# schema4.net
KiCad netlist of a schematic drawn in Altium Designer
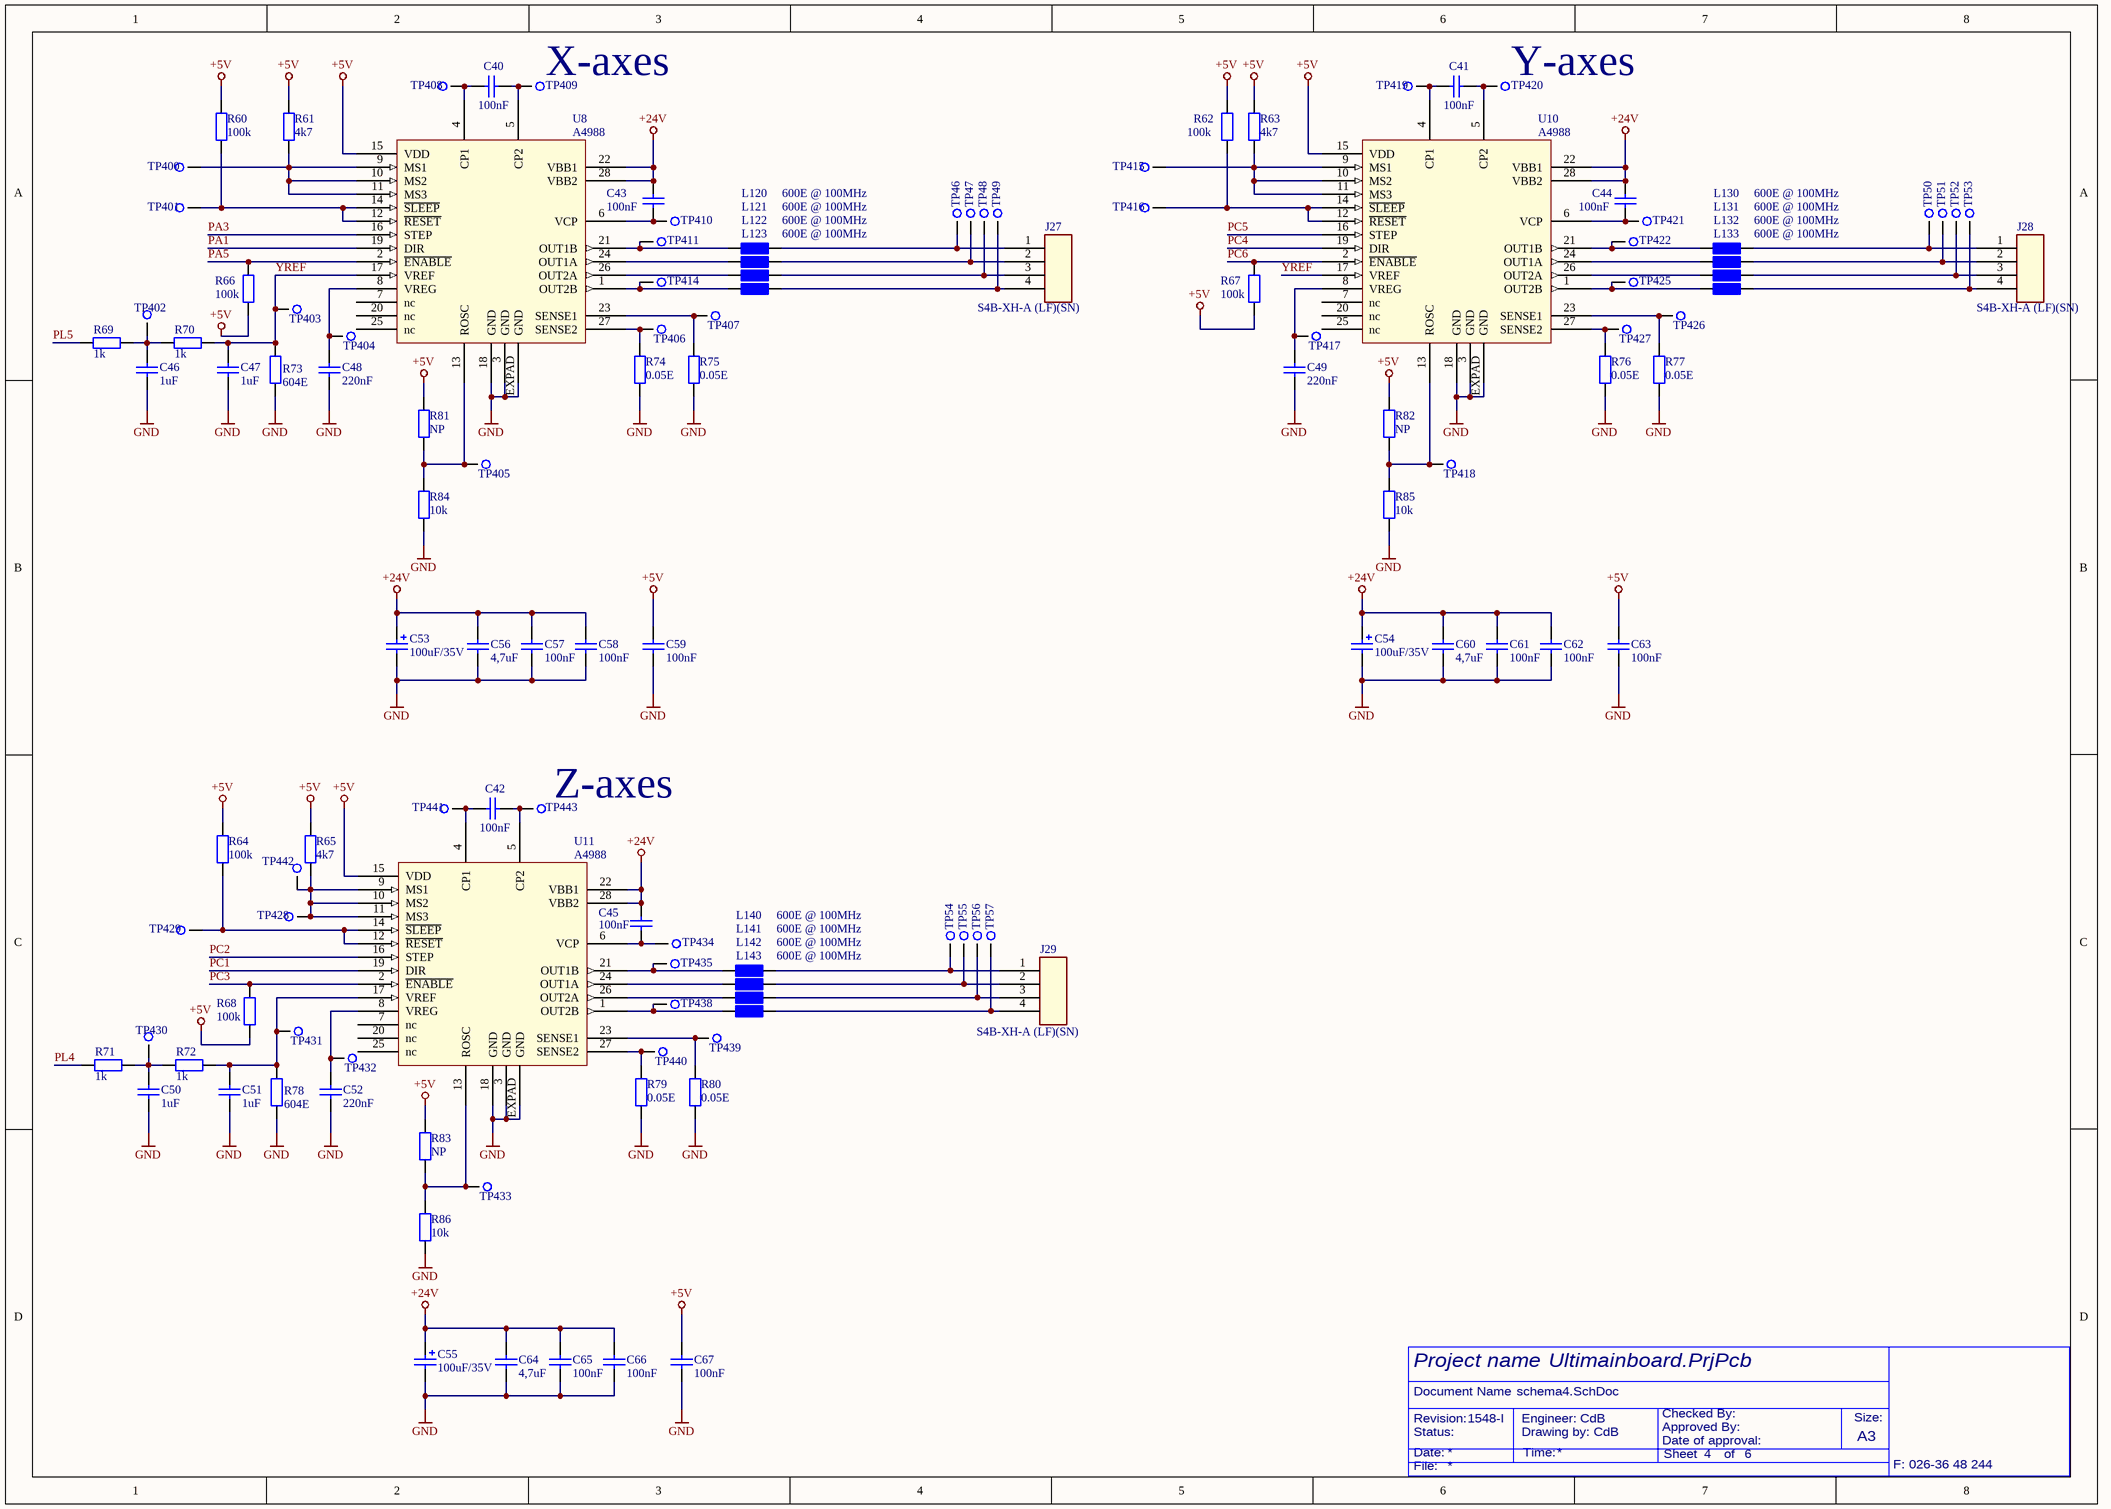
[diagram p0: schema4.SchDoc]

(export (version "E")
  (design (tool "Eeschema 10.0.6"))
  (components
    (comp (ref "C40")
      (value "100nF")
      (footprint "C0603")
      (description "RO X7R 100nF 10% 50V 0603")
      (libsource (lib "Database_Faber") (part "Capacitor"))
    )
    (comp (ref "C41")
      (value "100nF")
      (footprint "C0603")
      (description "RO X7R 100nF 10% 50V 0603")
      (libsource (lib "Database_Faber") (part "Capacitor"))
    )
    (comp (ref "C42")
      (value "100nF")
      (footprint "C0603")
      (description "RO X7R 100nF 10% 50V 0603")
      (libsource (lib "Database_Faber") (part "Capacitor"))
    )
    (comp (ref "C43")
      (value "100nF")
      (footprint "C0603")
      (description "RO X7R 100nF 10% 50V 0603")
      (libsource (lib "Database_Faber") (part "Capacitor"))
    )
    (comp (ref "C44")
      (value "100nF")
      (footprint "C0603")
      (description "RO X7R 100nF 10% 50V 0603")
      (libsource (lib "Database_Faber") (part "Capacitor"))
    )
    (comp (ref "C45")
      (value "100nF")
      (footprint "C0603")
      (description "RO X7R 100nF 10% 50V 0603")
      (libsource (lib "Database_Faber") (part "Capacitor"))
    )
    (comp (ref "C46")
      (value "1uF")
      (footprint "C0603")
      (description "RO X5R 1uF 10% 10V 0603")
      (libsource (lib "Database_Faber") (part "Capacitor"))
    )
    (comp (ref "C47")
      (value "1uF")
      (footprint "C0603")
      (description "RO X5R 1uF 10% 10V 0603")
      (libsource (lib "Database_Faber") (part "Capacitor"))
    )
    (comp (ref "C48")
      (value "220nF")
      (footprint "C0603")
      (description "RO X7R 220nF 10% 25V  0603")
      (libsource (lib "Database_Faber") (part "Capacitor"))
    )
    (comp (ref "C49")
      (value "220nF")
      (footprint "C0603")
      (description "RO X7R 220nF 10% 25V  0603")
      (libsource (lib "Database_Faber") (part "Capacitor"))
    )
    (comp (ref "C50")
      (value "1uF")
      (footprint "C0603")
      (description "RO X5R 1uF 10% 10V 0603")
      (libsource (lib "Database_Faber") (part "Capacitor"))
    )
    (comp (ref "C51")
      (value "1uF")
      (footprint "C0603")
      (description "RO X5R 1uF 10% 10V 0603")
      (libsource (lib "Database_Faber") (part "Capacitor"))
    )
    (comp (ref "C52")
      (value "220nF")
      (footprint "C0603")
      (description "RO X7R 220nF 10% 25V  0603")
      (libsource (lib "Database_Faber") (part "Capacitor"))
    )
    (comp (ref "C53")
      (value "100uF/35V")
      (footprint "ELCO Case D")
      (description "RO ELCO 100uF 20% 35V CASE-D EEEFP PAN")
      (libsource (lib "Database_Faber") (part "Capacitor Polarity"))
    )
    (comp (ref "C54")
      (value "100uF/35V")
      (footprint "ELCO Case D")
      (description "RO ELCO 100uF 20% 35V CASE-D EEEFP PAN")
      (libsource (lib "Database_Faber") (part "Capacitor Polarity"))
    )
    (comp (ref "C55")
      (value "100uF/35V")
      (footprint "ELCO Case D")
      (description "RO ELCO 100uF 20% 35V CASE-D EEEFP PAN")
      (libsource (lib "Database_Faber") (part "Capacitor Polarity"))
    )
    (comp (ref "C56")
      (value "4,7uF")
      (footprint "C1206")
      (description "RO X7R 4,7uF 10% 50V 1206")
      (libsource (lib "Database_Faber") (part "Capacitor"))
    )
    (comp (ref "C57")
      (value "100nF")
      (footprint "C0603")
      (description "RO X7R 100nF 10% 50V 0603")
      (libsource (lib "Database_Faber") (part "Capacitor"))
    )
    (comp (ref "C58")
      (value "100nF")
      (footprint "C0603")
      (description "RO X7R 100nF 10% 50V 0603")
      (libsource (lib "Database_Faber") (part "Capacitor"))
    )
    (comp (ref "C59")
      (value "100nF")
      (footprint "C0603")
      (description "RO X7R 100nF 10% 50V 0603")
      (libsource (lib "Database_Faber") (part "Capacitor"))
    )
    (comp (ref "C60")
      (value "4,7uF")
      (footprint "C1206")
      (description "RO X7R 4,7uF 10% 50V 1206")
      (libsource (lib "Database_Faber") (part "Capacitor"))
    )
    (comp (ref "C61")
      (value "100nF")
      (footprint "C0603")
      (description "RO X7R 100nF 10% 50V 0603")
      (libsource (lib "Database_Faber") (part "Capacitor"))
    )
    (comp (ref "C62")
      (value "100nF")
      (footprint "C0603")
      (description "RO X7R 100nF 10% 50V 0603")
      (libsource (lib "Database_Faber") (part "Capacitor"))
    )
    (comp (ref "C63")
      (value "100nF")
      (footprint "C0603")
      (description "RO X7R 100nF 10% 50V 0603")
      (libsource (lib "Database_Faber") (part "Capacitor"))
    )
    (comp (ref "C64")
      (value "4,7uF")
      (footprint "C1206")
      (description "RO X7R 4,7uF 10% 50V 1206")
      (libsource (lib "Database_Faber") (part "Capacitor"))
    )
    (comp (ref "C65")
      (value "100nF")
      (footprint "C0603")
      (description "RO X7R 100nF 10% 50V 0603")
      (libsource (lib "Database_Faber") (part "Capacitor"))
    )
    (comp (ref "C66")
      (value "100nF")
      (footprint "C0603")
      (description "RO X7R 100nF 10% 50V 0603")
      (libsource (lib "Database_Faber") (part "Capacitor"))
    )
    (comp (ref "C67")
      (value "100nF")
      (footprint "C0603")
      (description "RO X7R 100nF 10% 50V 0603")
      (libsource (lib "Database_Faber") (part "Capacitor"))
    )
    (comp (ref "J27")
      (value "S4B-XH-A (LF)(SN)")
      (footprint "S4B-XH-A (LF)(SN)")
      (description "RO CONN PR 4p HKS S4B-XH-A (LF)(SN) JST")
      (fields (field (name "MFG") "JST (JAPAN SOLDERLESS TERMINALS)"))
      (libsource (lib "Database_Faber") (part "HEADER 4"))
    )
    (comp (ref "J28")
      (value "S4B-XH-A (LF)(SN)")
      (footprint "S4B-XH-A (LF)(SN)")
      (description "RO CONN PR 4p HKS S4B-XH-A (LF)(SN) JST")
      (fields (field (name "MFG") "JST (JAPAN SOLDERLESS TERMINALS)"))
      (libsource (lib "Database_Faber") (part "HEADER 4"))
    )
    (comp (ref "J29")
      (value "S4B-XH-A (LF)(SN)")
      (footprint "S4B-XH-A (LF)(SN)")
      (description "RO CONN PR 4p HKS S4B-XH-A (LF)(SN) JST")
      (fields (field (name "MFG") "JST (JAPAN SOLDERLESS TERMINALS)"))
      (libsource (lib "Database_Faber") (part "HEADER 4"))
    )
    (comp (ref "L120")
      (value "600E @ 100MHz")
      (footprint "R1206")
      (description "FERRIET 742792118 1206 Wurth Elektronik")
      (fields (field (name "MFG") "Wurth Elektronics"))
      (libsource (lib "Ultimaker") (part "Ferriet Bead 600E"))
    )
    (comp (ref "L121")
      (value "600E @ 100MHz")
      (footprint "R1206")
      (description "FERRIET 742792118 1206 Wurth Elektronik")
      (fields (field (name "MFG") "Wurth Elektronics"))
      (libsource (lib "Ultimaker") (part "Ferriet Bead 600E"))
    )
    (comp (ref "L122")
      (value "600E @ 100MHz")
      (footprint "R1206")
      (description "FERRIET 742792118 1206 Wurth Elektronik")
      (fields (field (name "MFG") "Wurth Elektronics"))
      (libsource (lib "Ultimaker") (part "Ferriet Bead 600E"))
    )
    (comp (ref "L123")
      (value "600E @ 100MHz")
      (footprint "R1206")
      (description "FERRIET 742792118 1206 Wurth Elektronik")
      (fields (field (name "MFG") "Wurth Elektronics"))
      (libsource (lib "Ultimaker") (part "Ferriet Bead 600E"))
    )
    (comp (ref "L130")
      (value "600E @ 100MHz")
      (footprint "R1206")
      (description "FERRIET 742792118 1206 Wurth Elektronik")
      (fields (field (name "MFG") "Wurth Elektronics"))
      (libsource (lib "Ultimaker") (part "Ferriet Bead 600E"))
    )
    (comp (ref "L131")
      (value "600E @ 100MHz")
      (footprint "R1206")
      (description "FERRIET 742792118 1206 Wurth Elektronik")
      (fields (field (name "MFG") "Wurth Elektronics"))
      (libsource (lib "Ultimaker") (part "Ferriet Bead 600E"))
    )
    (comp (ref "L132")
      (value "600E @ 100MHz")
      (footprint "R1206")
      (description "FERRIET 742792118 1206 Wurth Elektronik")
      (fields (field (name "MFG") "Wurth Elektronics"))
      (libsource (lib "Ultimaker") (part "Ferriet Bead 600E"))
    )
    (comp (ref "L133")
      (value "600E @ 100MHz")
      (footprint "R1206")
      (description "FERRIET 742792118 1206 Wurth Elektronik")
      (fields (field (name "MFG") "Wurth Elektronics"))
      (libsource (lib "Ultimaker") (part "Ferriet Bead 600E"))
    )
    (comp (ref "L140")
      (value "600E @ 100MHz")
      (footprint "R1206")
      (description "FERRIET 742792118 1206 Wurth Elektronik")
      (fields (field (name "MFG") "Wurth Elektronics"))
      (libsource (lib "Ultimaker") (part "Ferriet Bead 600E"))
    )
    (comp (ref "L141")
      (value "600E @ 100MHz")
      (footprint "R1206")
      (description "FERRIET 742792118 1206 Wurth Elektronik")
      (fields (field (name "MFG") "Wurth Elektronics"))
      (libsource (lib "Ultimaker") (part "Ferriet Bead 600E"))
    )
    (comp (ref "L142")
      (value "600E @ 100MHz")
      (footprint "R1206")
      (description "FERRIET 742792118 1206 Wurth Elektronik")
      (fields (field (name "MFG") "Wurth Elektronics"))
      (libsource (lib "Ultimaker") (part "Ferriet Bead 600E"))
    )
    (comp (ref "L143")
      (value "600E @ 100MHz")
      (footprint "R1206")
      (description "FERRIET 742792118 1206 Wurth Elektronik")
      (fields (field (name "MFG") "Wurth Elektronics"))
      (libsource (lib "Ultimaker") (part "Ferriet Bead 600E"))
    )
    (comp (ref "R60")
      (value "100k")
      (footprint "R0603")
      (description "RO RES 100k0 1% 0,063W  0603")
      (libsource (lib "Database_Faber") (part "Resistor"))
    )
    (comp (ref "R61")
      (value "4k7")
      (footprint "R0603")
      (description "RO RES 4k70 1% 0,063W  0603")
      (libsource (lib "Database_Faber") (part "Resistor"))
    )
    (comp (ref "R62")
      (value "100k")
      (footprint "R0603")
      (description "RO RES 100k0 1% 0,063W  0603")
      (libsource (lib "Database_Faber") (part "Resistor"))
    )
    (comp (ref "R63")
      (value "4k7")
      (footprint "R0603")
      (description "RO RES 4k70 1% 0,063W  0603")
      (libsource (lib "Database_Faber") (part "Resistor"))
    )
    (comp (ref "R64")
      (value "100k")
      (footprint "R0603")
      (description "RO RES 100k0 1% 0,063W  0603")
      (libsource (lib "Database_Faber") (part "Resistor"))
    )
    (comp (ref "R65")
      (value "4k7")
      (footprint "R0603")
      (description "RO RES 4k70 1% 0,063W  0603")
      (libsource (lib "Database_Faber") (part "Resistor"))
    )
    (comp (ref "R66")
      (value "100k")
      (footprint "R0603")
      (description "RO RES 100k0 1% 0,063W  0603")
      (libsource (lib "") (part "Resistor_2"))
    )
    (comp (ref "R67")
      (value "100k")
      (footprint "R0603")
      (description "RO RES 100k0 1% 0,063W  0603")
      (libsource (lib "") (part "Resistor_2"))
    )
    (comp (ref "R68")
      (value "100k")
      (footprint "R0603")
      (description "RO RES 100k0 1% 0,063W  0603")
      (libsource (lib "") (part "Resistor_2"))
    )
    (comp (ref "R69")
      (value "1k")
      (footprint "R0603")
      (description "RO RES 1k0 1% 0,1W  0603")
      (libsource (lib "") (part "Resistor_1"))
    )
    (comp (ref "R70")
      (value "1k")
      (footprint "R0603")
      (description "RO RES 1k0 1% 0,1W  0603")
      (libsource (lib "") (part "Resistor_1"))
    )
    (comp (ref "R71")
      (value "1k")
      (footprint "R0603")
      (description "RO RES 1k0 1% 0,1W  0603")
      (libsource (lib "") (part "Resistor_1"))
    )
    (comp (ref "R72")
      (value "1k")
      (footprint "R0603")
      (description "RO RES 1k0 1% 0,1W  0603")
      (libsource (lib "") (part "Resistor_1"))
    )
    (comp (ref "R73")
      (value "604E")
      (footprint "R0603")
      (description "RO RES 604E 1% 0,063W 0603")
      (fields (field (name "MFG") "VISHAY DRALORIC"))
      (libsource (lib "Database_Faber") (part "Resistor"))
    )
    (comp (ref "R74")
      (value "0.05E")
      (footprint "R0805")
      (description "RO RES 0E05 1% 0,125W 0805")
      (fields (field (name "MFG") "BOURNS"))
      (libsource (lib "Database_Faber") (part "Resistor"))
    )
    (comp (ref "R75")
      (value "0.05E")
      (footprint "R0805")
      (description "RO RES 0E05 1% 0,125W 0805")
      (fields (field (name "MFG") "BOURNS"))
      (libsource (lib "Database_Faber") (part "Resistor"))
    )
    (comp (ref "R76")
      (value "0.05E")
      (footprint "R0805")
      (description "RO RES 0E05 1% 0,125W 0805")
      (fields (field (name "MFG") "BOURNS"))
      (libsource (lib "Database_Faber") (part "Resistor"))
    )
    (comp (ref "R77")
      (value "0.05E")
      (footprint "R0805")
      (description "RO RES 0E05 1% 0,125W 0805")
      (fields (field (name "MFG") "BOURNS"))
      (libsource (lib "Database_Faber") (part "Resistor"))
    )
    (comp (ref "R78")
      (value "604E")
      (footprint "R0603")
      (description "RO RES 604E 1% 0,063W 0603")
      (fields (field (name "MFG") "VISHAY DRALORIC"))
      (libsource (lib "Database_Faber") (part "Resistor"))
    )
    (comp (ref "R79")
      (value "0.05E")
      (footprint "R0805")
      (description "RO RES 0E05 1% 0,125W 0805")
      (fields (field (name "MFG") "BOURNS"))
      (libsource (lib "Database_Faber") (part "Resistor"))
    )
    (comp (ref "R80")
      (value "0.05E")
      (footprint "R0805")
      (description "RO RES 0E05 1% 0,125W 0805")
      (fields (field (name "MFG") "BOURNS"))
      (libsource (lib "Database_Faber") (part "Resistor"))
    )
    (comp (ref "R81") (value "NP") (footprint "R0603") (libsource (lib "Database_Faber") (part "Resistor")))
    (comp (ref "R82") (value "NP") (footprint "R0603") (libsource (lib "Database_Faber") (part "Resistor")))
    (comp (ref "R83") (value "NP") (footprint "R0603") (libsource (lib "Database_Faber") (part "Resistor")))
    (comp (ref "R84")
      (value "10k")
      (footprint "R0603")
      (description "RO RES 10k0 1% 0,063W  0603")
      (libsource (lib "Database_Faber") (part "Resistor"))
    )
    (comp (ref "R85")
      (value "10k")
      (footprint "R0603")
      (description "RO RES 10k0 1% 0,063W  0603")
      (libsource (lib "Database_Faber") (part "Resistor"))
    )
    (comp (ref "R86")
      (value "10k")
      (footprint "R0603")
      (description "RO RES 10k0 1% 0,063W  0603")
      (libsource (lib "Database_Faber") (part "Resistor"))
    )
    (comp (ref "TP46")
      (value "Testpoint")
      (footprint "Testpoint")
      (libsource (lib "Database_Faber") (part "Testpoint"))
    )
    (comp (ref "TP47")
      (value "Testpoint")
      (footprint "Testpoint")
      (libsource (lib "Database_Faber") (part "Testpoint"))
    )
    (comp (ref "TP48")
      (value "Testpoint")
      (footprint "Testpoint")
      (libsource (lib "Database_Faber") (part "Testpoint"))
    )
    (comp (ref "TP49")
      (value "Testpoint")
      (footprint "Testpoint")
      (libsource (lib "Database_Faber") (part "Testpoint"))
    )
    (comp (ref "TP50")
      (value "Testpoint")
      (footprint "Testpoint")
      (libsource (lib "Database_Faber") (part "Testpoint"))
    )
    (comp (ref "TP51")
      (value "Testpoint")
      (footprint "Testpoint")
      (libsource (lib "Database_Faber") (part "Testpoint"))
    )
    (comp (ref "TP52")
      (value "Testpoint")
      (footprint "Testpoint")
      (libsource (lib "Database_Faber") (part "Testpoint"))
    )
    (comp (ref "TP53")
      (value "Testpoint")
      (footprint "Testpoint")
      (libsource (lib "Database_Faber") (part "Testpoint"))
    )
    (comp (ref "TP54")
      (value "Testpoint")
      (footprint "Testpoint")
      (libsource (lib "Database_Faber") (part "Testpoint"))
    )
    (comp (ref "TP55")
      (value "Testpoint")
      (footprint "Testpoint")
      (libsource (lib "Database_Faber") (part "Testpoint"))
    )
    (comp (ref "TP56")
      (value "Testpoint")
      (footprint "Testpoint")
      (libsource (lib "Database_Faber") (part "Testpoint"))
    )
    (comp (ref "TP57")
      (value "Testpoint")
      (footprint "Testpoint")
      (libsource (lib "Database_Faber") (part "Testpoint"))
    )
    (comp (ref "TP400")
      (value "Testpoint")
      (footprint "TESTPOINT")
      (libsource (lib "Ultimaker") (part "Testpoint 1mm"))
    )
    (comp (ref "TP401")
      (value "Testpoint")
      (footprint "TESTPOINT")
      (libsource (lib "Ultimaker") (part "Testpoint 1mm"))
    )
    (comp (ref "TP402")
      (value "Testpoint 1mm")
      (footprint "Testpoint 1mm")
      (libsource (lib "Ultimaker") (part "Testpoint 1mm"))
    )
    (comp (ref "TP403")
      (value "Testpoint 1mm")
      (footprint "Testpoint 1mm")
      (libsource (lib "Ultimaker") (part "Testpoint 1mm"))
    )
    (comp (ref "TP404")
      (value "Testpoint 1mm")
      (footprint "Testpoint 1mm")
      (libsource (lib "Ultimaker") (part "Testpoint 1mm"))
    )
    (comp (ref "TP405")
      (value "Testpoint 1mm")
      (footprint "Testpoint 1mm")
      (libsource (lib "Ultimaker") (part "Testpoint 1mm"))
    )
    (comp (ref "TP406")
      (value "Testpoint 1mm")
      (footprint "Testpoint 1mm")
      (libsource (lib "Ultimaker") (part "Testpoint 1mm"))
    )
    (comp (ref "TP407")
      (value "Testpoint 1mm")
      (footprint "Testpoint 1mm")
      (libsource (lib "Ultimaker") (part "Testpoint 1mm"))
    )
    (comp (ref "TP408")
      (value "Testpoint 1mm")
      (footprint "Testpoint 1mm")
      (libsource (lib "Ultimaker") (part "Testpoint 1mm"))
    )
    (comp (ref "TP409")
      (value "Testpoint 1mm")
      (footprint "Testpoint 1mm")
      (libsource (lib "Ultimaker") (part "Testpoint 1mm"))
    )
    (comp (ref "TP410")
      (value "Testpoint 1mm")
      (footprint "Testpoint 1mm")
      (libsource (lib "Ultimaker") (part "Testpoint 1mm"))
    )
    (comp (ref "TP411")
      (value "Testpoint 1mm")
      (footprint "Testpoint 1mm")
      (libsource (lib "Ultimaker") (part "Testpoint 1mm"))
    )
    (comp (ref "TP414")
      (value "Testpoint 1mm")
      (footprint "Testpoint 1mm")
      (libsource (lib "Ultimaker") (part "Testpoint 1mm"))
    )
    (comp (ref "TP415")
      (value "Testpoint")
      (footprint "TESTPOINT")
      (libsource (lib "Ultimaker") (part "Testpoint 1mm"))
    )
    (comp (ref "TP416")
      (value "Testpoint")
      (footprint "TESTPOINT")
      (libsource (lib "Ultimaker") (part "Testpoint 1mm"))
    )
    (comp (ref "TP417")
      (value "Testpoint 1mm")
      (footprint "Testpoint 1mm")
      (libsource (lib "Ultimaker") (part "Testpoint 1mm"))
    )
    (comp (ref "TP418")
      (value "Testpoint 1mm")
      (footprint "Testpoint 1mm")
      (libsource (lib "Ultimaker") (part "Testpoint 1mm"))
    )
    (comp (ref "TP419")
      (value "Testpoint 1mm")
      (footprint "Testpoint 1mm")
      (libsource (lib "Ultimaker") (part "Testpoint 1mm"))
    )
    (comp (ref "TP420")
      (value "Testpoint 1mm")
      (footprint "Testpoint 1mm")
      (libsource (lib "Ultimaker") (part "Testpoint 1mm"))
    )
    (comp (ref "TP421")
      (value "Testpoint 1mm")
      (footprint "Testpoint 1mm")
      (libsource (lib "Ultimaker") (part "Testpoint 1mm"))
    )
    (comp (ref "TP422")
      (value "Testpoint 1mm")
      (footprint "Testpoint 1mm")
      (libsource (lib "Ultimaker") (part "Testpoint 1mm"))
    )
    (comp (ref "TP425")
      (value "Testpoint 1mm")
      (footprint "Testpoint 1mm")
      (libsource (lib "Ultimaker") (part "Testpoint 1mm"))
    )
    (comp (ref "TP426")
      (value "Testpoint 1mm")
      (footprint "Testpoint 1mm")
      (libsource (lib "Ultimaker") (part "Testpoint 1mm"))
    )
    (comp (ref "TP427")
      (value "Testpoint 1mm")
      (footprint "Testpoint 1mm")
      (libsource (lib "Ultimaker") (part "Testpoint 1mm"))
    )
    (comp (ref "TP428")
      (value "Testpoint")
      (footprint "TESTPOINT")
      (libsource (lib "Ultimaker") (part "Testpoint 1mm"))
    )
    (comp (ref "TP429")
      (value "Testpoint")
      (footprint "TESTPOINT")
      (libsource (lib "Ultimaker") (part "Testpoint 1mm"))
    )
    (comp (ref "TP430")
      (value "Testpoint 1mm")
      (footprint "Testpoint 1mm")
      (libsource (lib "Ultimaker") (part "Testpoint 1mm"))
    )
    (comp (ref "TP431")
      (value "Testpoint 1mm")
      (footprint "Testpoint 1mm")
      (libsource (lib "Ultimaker") (part "Testpoint 1mm"))
    )
    (comp (ref "TP432")
      (value "Testpoint 1mm")
      (footprint "Testpoint 1mm")
      (libsource (lib "Ultimaker") (part "Testpoint 1mm"))
    )
    (comp (ref "TP433")
      (value "Testpoint 1mm")
      (footprint "Testpoint 1mm")
      (libsource (lib "Ultimaker") (part "Testpoint 1mm"))
    )
    (comp (ref "TP434")
      (value "Testpoint 1mm")
      (footprint "Testpoint 1mm")
      (libsource (lib "Ultimaker") (part "Testpoint 1mm"))
    )
    (comp (ref "TP435")
      (value "Testpoint 1mm")
      (footprint "Testpoint 1mm")
      (libsource (lib "Ultimaker") (part "Testpoint 1mm"))
    )
    (comp (ref "TP438")
      (value "Testpoint 1mm")
      (footprint "Testpoint 1mm")
      (libsource (lib "Ultimaker") (part "Testpoint 1mm"))
    )
    (comp (ref "TP439")
      (value "Testpoint 1mm")
      (footprint "Testpoint 1mm")
      (libsource (lib "Ultimaker") (part "Testpoint 1mm"))
    )
    (comp (ref "TP440")
      (value "Testpoint 1mm")
      (footprint "Testpoint 1mm")
      (libsource (lib "Ultimaker") (part "Testpoint 1mm"))
    )
    (comp (ref "TP441")
      (value "Testpoint 1mm")
      (footprint "Testpoint 1mm")
      (libsource (lib "Ultimaker") (part "Testpoint 1mm"))
    )
    (comp (ref "TP442")
      (value "Testpoint")
      (footprint "TESTPOINT")
      (libsource (lib "Ultimaker") (part "Testpoint 1mm"))
    )
    (comp (ref "TP443")
      (value "Testpoint 1mm")
      (footprint "Testpoint 1mm")
      (libsource (lib "Ultimaker") (part "Testpoint 1mm"))
    )
    (comp (ref "U8")
      (value "A4988")
      (footprint "QFN50P500X500X100-28-EX")
      (description "RO IC A4988 QFN-28 ALLEGRO")
      (fields (field (name "MFG") "Allegro"))
      (libsource (lib "Database_Faber") (part "A4988"))
    )
    (comp (ref "U10")
      (value "A4988")
      (footprint "QFN50P500X500X100-28-EX")
      (description "RO IC A4988 QFN-28 ALLEGRO")
      (fields (field (name "MFG") "Allegro"))
      (libsource (lib "Database_Faber") (part "A4988"))
    )
    (comp (ref "U11")
      (value "A4988")
      (footprint "QFN50P500X500X100-28-EX")
      (description "RO IC A4988 QFN-28 ALLEGRO")
      (fields (field (name "MFG") "Allegro"))
      (libsource (lib "Database_Faber") (part "A4988"))
    )
  )
  (nets
    (net (code "1") (name "+5V") (class "Default")
      (node (ref "C59") (pin "2") (pinfunction "2_2") (pintype "passive"))
      (node (ref "C63") (pin "2") (pinfunction "2_2") (pintype "passive"))
      (node (ref "C67") (pin "2") (pinfunction "2_2") (pintype "passive"))
      (node (ref "R60") (pin "2") (pinfunction "2_2") (pintype "passive"))
      (node (ref "R61") (pin "2") (pinfunction "2_2") (pintype "passive"))
      (node (ref "R62") (pin "2") (pinfunction "2_2") (pintype "passive"))
      (node (ref "R63") (pin "2") (pinfunction "2_2") (pintype "passive"))
      (node (ref "R64") (pin "2") (pinfunction "2_2") (pintype "passive"))
      (node (ref "R65") (pin "2") (pinfunction "2_2") (pintype "passive"))
      (node (ref "R66") (pin "2") (pinfunction "2_2") (pintype "passive"))
      (node (ref "R67") (pin "2") (pinfunction "2_2") (pintype "passive"))
      (node (ref "R68") (pin "2") (pinfunction "2_2") (pintype "passive"))
      (node (ref "R81") (pin "2") (pinfunction "2_2") (pintype "passive"))
      (node (ref "R82") (pin "2") (pinfunction "2_2") (pintype "passive"))
      (node (ref "R83") (pin "2") (pinfunction "2_2") (pintype "passive"))
      (node (ref "U10") (pin "15") (pinfunction "VDD_15") (pintype "power_in"))
      (node (ref "U11") (pin "15") (pinfunction "VDD_15") (pintype "power_in"))
      (node (ref "U8") (pin "15") (pinfunction "VDD_15") (pintype "power_in"))
    )
    (net (code "2") (name "+24V") (class "Default")
      (node (ref "C43") (pin "2") (pinfunction "2_2") (pintype "passive"))
      (node (ref "C44") (pin "2") (pinfunction "2_2") (pintype "passive"))
      (node (ref "C45") (pin "2") (pinfunction "2_2") (pintype "passive"))
      (node (ref "C53") (pin "1") (pinfunction "1_1") (pintype "passive"))
      (node (ref "C54") (pin "1") (pinfunction "1_1") (pintype "passive"))
      (node (ref "C55") (pin "1") (pinfunction "1_1") (pintype "passive"))
      (node (ref "C56") (pin "2") (pinfunction "2_2") (pintype "passive"))
      (node (ref "C57") (pin "2") (pinfunction "2_2") (pintype "passive"))
      (node (ref "C58") (pin "2") (pinfunction "2_2") (pintype "passive"))
      (node (ref "C60") (pin "2") (pinfunction "2_2") (pintype "passive"))
      (node (ref "C61") (pin "2") (pinfunction "2_2") (pintype "passive"))
      (node (ref "C62") (pin "2") (pinfunction "2_2") (pintype "passive"))
      (node (ref "C64") (pin "2") (pinfunction "2_2") (pintype "passive"))
      (node (ref "C65") (pin "2") (pinfunction "2_2") (pintype "passive"))
      (node (ref "C66") (pin "2") (pinfunction "2_2") (pintype "passive"))
      (node (ref "U10") (pin "22") (pinfunction "VBB1_22") (pintype "power_in"))
      (node (ref "U10") (pin "28") (pinfunction "VBB2_28") (pintype "power_in"))
      (node (ref "U11") (pin "22") (pinfunction "VBB1_22") (pintype "power_in"))
      (node (ref "U11") (pin "28") (pinfunction "VBB2_28") (pintype "power_in"))
      (node (ref "U8") (pin "22") (pinfunction "VBB1_22") (pintype "power_in"))
      (node (ref "U8") (pin "28") (pinfunction "VBB2_28") (pintype "power_in"))
    )
    (net (code "3") (name "/PA1") (class "Default")
      (node (ref "U8") (pin "19") (pinfunction "DIR_19") (pintype "input"))
    )
    (net (code "4") (name "/PA3") (class "Default")
      (node (ref "U8") (pin "16") (pinfunction "STEP_16") (pintype "input"))
    )
    (net (code "5") (name "/PA5") (class "Default")
      (node (ref "R66") (pin "1") (pinfunction "1_1") (pintype "passive"))
      (node (ref "U8") (pin "2") (pinfunction "~{ENABLE}_2") (pintype "input"))
    )
    (net (code "6") (name "/PC1") (class "Default")
      (node (ref "U11") (pin "19") (pinfunction "DIR_19") (pintype "input"))
    )
    (net (code "7") (name "/PC2") (class "Default")
      (node (ref "U11") (pin "16") (pinfunction "STEP_16") (pintype "input"))
    )
    (net (code "8") (name "/PC3") (class "Default")
      (node (ref "R68") (pin "1") (pinfunction "1_1") (pintype "passive"))
      (node (ref "U11") (pin "2") (pinfunction "~{ENABLE}_2") (pintype "input"))
    )
    (net (code "9") (name "/PC4") (class "Default")
      (node (ref "U10") (pin "19") (pinfunction "DIR_19") (pintype "input"))
    )
    (net (code "10") (name "/PC5") (class "Default")
      (node (ref "U10") (pin "16") (pinfunction "STEP_16") (pintype "input"))
    )
    (net (code "11") (name "/PC6") (class "Default")
      (node (ref "R67") (pin "1") (pinfunction "1_1") (pintype "passive"))
      (node (ref "U10") (pin "2") (pinfunction "~{ENABLE}_2") (pintype "input"))
    )
    (net (code "12") (name "/PL4") (class "Default")
      (node (ref "R71") (pin "1") (pinfunction "1_1") (pintype "passive"))
    )
    (net (code "13") (name "/PL5") (class "Default")
      (node (ref "R69") (pin "1") (pinfunction "1_1") (pintype "passive"))
    )
    (net (code "14") (name "/YREF") (class "Default")
      (node (ref "C47") (pin "2") (pinfunction "2_2") (pintype "passive"))
      (node (ref "R70") (pin "2") (pinfunction "2_2") (pintype "passive"))
      (node (ref "R73") (pin "2") (pinfunction "2_2") (pintype "passive"))
      (node (ref "TP403") (pin "1") (pinfunction "1_1") (pintype "passive"))
      (node (ref "U10") (pin "17") (pinfunction "VREF_17") (pintype "input"))
      (node (ref "U8") (pin "17") (pinfunction "VREF_17") (pintype "input"))
    )
    (net (code "15") (name "GND") (class "Default")
      (node (ref "C46") (pin "1") (pinfunction "1_1") (pintype "passive"))
      (node (ref "C47") (pin "1") (pinfunction "1_1") (pintype "passive"))
      (node (ref "C48") (pin "1") (pinfunction "1_1") (pintype "passive"))
      (node (ref "C49") (pin "1") (pinfunction "1_1") (pintype "passive"))
      (node (ref "C50") (pin "1") (pinfunction "1_1") (pintype "passive"))
      (node (ref "C51") (pin "1") (pinfunction "1_1") (pintype "passive"))
      (node (ref "C52") (pin "1") (pinfunction "1_1") (pintype "passive"))
      (node (ref "C53") (pin "2") (pinfunction "2_2") (pintype "passive"))
      (node (ref "C54") (pin "2") (pinfunction "2_2") (pintype "passive"))
      (node (ref "C55") (pin "2") (pinfunction "2_2") (pintype "passive"))
      (node (ref "C56") (pin "1") (pinfunction "1_1") (pintype "passive"))
      (node (ref "C57") (pin "1") (pinfunction "1_1") (pintype "passive"))
      (node (ref "C58") (pin "1") (pinfunction "1_1") (pintype "passive"))
      (node (ref "C59") (pin "1") (pinfunction "1_1") (pintype "passive"))
      (node (ref "C60") (pin "1") (pinfunction "1_1") (pintype "passive"))
      (node (ref "C61") (pin "1") (pinfunction "1_1") (pintype "passive"))
      (node (ref "C62") (pin "1") (pinfunction "1_1") (pintype "passive"))
      (node (ref "C63") (pin "1") (pinfunction "1_1") (pintype "passive"))
      (node (ref "C64") (pin "1") (pinfunction "1_1") (pintype "passive"))
      (node (ref "C65") (pin "1") (pinfunction "1_1") (pintype "passive"))
      (node (ref "C66") (pin "1") (pinfunction "1_1") (pintype "passive"))
      (node (ref "C67") (pin "1") (pinfunction "1_1") (pintype "passive"))
      (node (ref "R73") (pin "1") (pinfunction "1_1") (pintype "passive"))
      (node (ref "R74") (pin "1") (pinfunction "1_1") (pintype "passive"))
      (node (ref "R75") (pin "1") (pinfunction "1_1") (pintype "passive"))
      (node (ref "R76") (pin "1") (pinfunction "1_1") (pintype "passive"))
      (node (ref "R77") (pin "1") (pinfunction "1_1") (pintype "passive"))
      (node (ref "R78") (pin "1") (pinfunction "1_1") (pintype "passive"))
      (node (ref "R79") (pin "1") (pinfunction "1_1") (pintype "passive"))
      (node (ref "R80") (pin "1") (pinfunction "1_1") (pintype "passive"))
      (node (ref "R84") (pin "1") (pinfunction "1_1") (pintype "passive"))
      (node (ref "R85") (pin "1") (pinfunction "1_1") (pintype "passive"))
      (node (ref "R86") (pin "1") (pinfunction "1_1") (pintype "passive"))
      (node (ref "U10") (pin "18") (pinfunction "GND_18") (pintype "passive"))
      (node (ref "U10") (pin "3") (pinfunction "GND_3") (pintype "power_in"))
      (node (ref "U10") (pin "EXPAD") (pinfunction "GND_EXPAD") (pintype "power_in"))
      (node (ref "U11") (pin "18") (pinfunction "GND_18") (pintype "passive"))
      (node (ref "U11") (pin "3") (pinfunction "GND_3") (pintype "power_in"))
      (node (ref "U11") (pin "EXPAD") (pinfunction "GND_EXPAD") (pintype "power_in"))
      (node (ref "U8") (pin "18") (pinfunction "GND_18") (pintype "passive"))
      (node (ref "U8") (pin "3") (pinfunction "GND_3") (pintype "power_in"))
      (node (ref "U8") (pin "EXPAD") (pinfunction "GND_EXPAD") (pintype "power_in"))
    )
    (net (code "16") (name "Net-(C46-Pad2)") (class "Default")
      (node (ref "C46") (pin "2") (pinfunction "2_2") (pintype "passive"))
      (node (ref "R69") (pin "2") (pinfunction "2_2") (pintype "passive"))
      (node (ref "R70") (pin "1") (pinfunction "1_1") (pintype "passive"))
      (node (ref "TP402") (pin "1") (pinfunction "1_1") (pintype "passive"))
    )
    (net (code "17") (name "Net-(C50-Pad2)") (class "Default")
      (node (ref "C50") (pin "2") (pinfunction "2_2") (pintype "passive"))
      (node (ref "R71") (pin "2") (pinfunction "2_2") (pintype "passive"))
      (node (ref "R72") (pin "1") (pinfunction "1_1") (pintype "passive"))
      (node (ref "TP430") (pin "1") (pinfunction "1_1") (pintype "passive"))
    )
    (net (code "18") (name "Net-(J27-Pad1)") (class "Default")
      (node (ref "J27") (pin "1") (pinfunction "1_1") (pintype "passive"))
      (node (ref "L120") (pin "2") (pinfunction "2_2") (pintype "passive"))
      (node (ref "TP46") (pin "1") (pinfunction "1_1") (pintype "passive"))
    )
    (net (code "19") (name "Net-(J27-Pad2)") (class "Default")
      (node (ref "J27") (pin "2") (pinfunction "2_2") (pintype "passive"))
      (node (ref "L121") (pin "2") (pinfunction "2_2") (pintype "passive"))
      (node (ref "TP47") (pin "1") (pinfunction "1_1") (pintype "passive"))
    )
    (net (code "20") (name "Net-(J27-Pad3)") (class "Default")
      (node (ref "J27") (pin "3") (pinfunction "3_3") (pintype "passive"))
      (node (ref "L122") (pin "2") (pinfunction "2_2") (pintype "passive"))
      (node (ref "TP48") (pin "1") (pinfunction "1_1") (pintype "passive"))
    )
    (net (code "21") (name "Net-(J27-Pad4)") (class "Default")
      (node (ref "J27") (pin "4") (pinfunction "4_4") (pintype "passive"))
      (node (ref "L123") (pin "2") (pinfunction "2_2") (pintype "passive"))
      (node (ref "TP49") (pin "1") (pinfunction "1_1") (pintype "passive"))
    )
    (net (code "22") (name "Net-(J28-Pad1)") (class "Default")
      (node (ref "J28") (pin "1") (pinfunction "1_1") (pintype "passive"))
      (node (ref "L130") (pin "2") (pinfunction "2_2") (pintype "passive"))
      (node (ref "TP50") (pin "1") (pinfunction "1_1") (pintype "passive"))
    )
    (net (code "23") (name "Net-(J28-Pad2)") (class "Default")
      (node (ref "J28") (pin "2") (pinfunction "2_2") (pintype "passive"))
      (node (ref "L131") (pin "2") (pinfunction "2_2") (pintype "passive"))
      (node (ref "TP51") (pin "1") (pinfunction "1_1") (pintype "passive"))
    )
    (net (code "24") (name "Net-(J28-Pad3)") (class "Default")
      (node (ref "J28") (pin "3") (pinfunction "3_3") (pintype "passive"))
      (node (ref "L132") (pin "2") (pinfunction "2_2") (pintype "passive"))
      (node (ref "TP52") (pin "1") (pinfunction "1_1") (pintype "passive"))
    )
    (net (code "25") (name "Net-(J28-Pad4)") (class "Default")
      (node (ref "J28") (pin "4") (pinfunction "4_4") (pintype "passive"))
      (node (ref "L133") (pin "2") (pinfunction "2_2") (pintype "passive"))
      (node (ref "TP53") (pin "1") (pinfunction "1_1") (pintype "passive"))
    )
    (net (code "26") (name "Net-(J29-Pad1)") (class "Default")
      (node (ref "J29") (pin "1") (pinfunction "1_1") (pintype "passive"))
      (node (ref "L140") (pin "2") (pinfunction "2_2") (pintype "passive"))
      (node (ref "TP54") (pin "1") (pinfunction "1_1") (pintype "passive"))
    )
    (net (code "27") (name "Net-(J29-Pad2)") (class "Default")
      (node (ref "J29") (pin "2") (pinfunction "2_2") (pintype "passive"))
      (node (ref "L141") (pin "2") (pinfunction "2_2") (pintype "passive"))
      (node (ref "TP55") (pin "1") (pinfunction "1_1") (pintype "passive"))
    )
    (net (code "28") (name "Net-(J29-Pad3)") (class "Default")
      (node (ref "J29") (pin "3") (pinfunction "3_3") (pintype "passive"))
      (node (ref "L142") (pin "2") (pinfunction "2_2") (pintype "passive"))
      (node (ref "TP56") (pin "1") (pinfunction "1_1") (pintype "passive"))
    )
    (net (code "29") (name "Net-(J29-Pad4)") (class "Default")
      (node (ref "J29") (pin "4") (pinfunction "4_4") (pintype "passive"))
      (node (ref "L143") (pin "2") (pinfunction "2_2") (pintype "passive"))
      (node (ref "TP57") (pin "1") (pinfunction "1_1") (pintype "passive"))
    )
    (net (code "30") (name "Net-(U8-CP1)") (class "Default")
      (node (ref "C40") (pin "1") (pinfunction "1_1") (pintype "passive"))
      (node (ref "TP408") (pin "1") (pinfunction "1_1") (pintype "passive"))
      (node (ref "U8") (pin "4") (pinfunction "CP1_4") (pintype "passive"))
    )
    (net (code "31") (name "Net-(U8-CP2)") (class "Default")
      (node (ref "C40") (pin "2") (pinfunction "2_2") (pintype "passive"))
      (node (ref "TP409") (pin "1") (pinfunction "1_1") (pintype "passive"))
      (node (ref "U8") (pin "5") (pinfunction "CP2_5") (pintype "passive"))
    )
    (net (code "32") (name "Net-(U8-MS1)") (class "Default")
      (node (ref "R61") (pin "1") (pinfunction "1_1") (pintype "passive"))
      (node (ref "TP400") (pin "1") (pinfunction "1_1") (pintype "passive"))
      (node (ref "U8") (pin "10") (pinfunction "MS2_10") (pintype "input"))
      (node (ref "U8") (pin "11") (pinfunction "MS3_11") (pintype "input"))
      (node (ref "U8") (pin "9") (pinfunction "MS1_9") (pintype "input"))
    )
    (net (code "33") (name "Net-(U8-OUT1A)") (class "Default")
      (node (ref "L121") (pin "1") (pinfunction "1_1") (pintype "passive"))
      (node (ref "U8") (pin "24") (pinfunction "OUT1A_24") (pintype "output"))
    )
    (net (code "34") (name "Net-(U8-OUT1B)") (class "Default")
      (node (ref "L120") (pin "1") (pinfunction "1_1") (pintype "passive"))
      (node (ref "TP411") (pin "1") (pinfunction "1_1") (pintype "passive"))
      (node (ref "U8") (pin "21") (pinfunction "OUT1B_21") (pintype "output"))
    )
    (net (code "35") (name "Net-(U8-OUT2A)") (class "Default")
      (node (ref "L122") (pin "1") (pinfunction "1_1") (pintype "passive"))
      (node (ref "U8") (pin "26") (pinfunction "OUT2A_26") (pintype "output"))
    )
    (net (code "36") (name "Net-(U8-OUT2B)") (class "Default")
      (node (ref "L123") (pin "1") (pinfunction "1_1") (pintype "passive"))
      (node (ref "TP414") (pin "1") (pinfunction "1_1") (pintype "passive"))
      (node (ref "U8") (pin "1") (pinfunction "OUT2B_1") (pintype "output"))
    )
    (net (code "37") (name "Net-(U8-ROSC)") (class "Default")
      (node (ref "R81") (pin "1") (pinfunction "1_1") (pintype "passive"))
      (node (ref "R84") (pin "2") (pinfunction "2_2") (pintype "passive"))
      (node (ref "TP405") (pin "1") (pinfunction "1_1") (pintype "passive"))
      (node (ref "U8") (pin "13") (pinfunction "ROSC_13") (pintype "passive"))
    )
    (net (code "38") (name "Net-(U8-SENSE1)") (class "Default")
      (node (ref "R75") (pin "2") (pinfunction "2_2") (pintype "passive"))
      (node (ref "TP407") (pin "1") (pinfunction "1_1") (pintype "passive"))
      (node (ref "U8") (pin "23") (pinfunction "SENSE1_23") (pintype "passive"))
    )
    (net (code "39") (name "Net-(U8-SENSE2)") (class "Default")
      (node (ref "R74") (pin "2") (pinfunction "2_2") (pintype "passive"))
      (node (ref "TP406") (pin "1") (pinfunction "1_1") (pintype "passive"))
      (node (ref "U8") (pin "27") (pinfunction "SENSE2_27") (pintype "passive"))
    )
    (net (code "40") (name "Net-(U8-VCP)") (class "Default")
      (node (ref "C43") (pin "1") (pinfunction "1_1") (pintype "passive"))
      (node (ref "TP410") (pin "1") (pinfunction "1_1") (pintype "passive"))
      (node (ref "U8") (pin "6") (pinfunction "VCP_6") (pintype "passive"))
    )
    (net (code "41") (name "Net-(U8-VREG)") (class "Default")
      (node (ref "C48") (pin "2") (pinfunction "2_2") (pintype "passive"))
      (node (ref "TP404") (pin "1") (pinfunction "1_1") (pintype "passive"))
      (node (ref "U8") (pin "8") (pinfunction "VREG_8") (pintype "power_in"))
    )
    (net (code "42") (name "Net-(U8-~{RESET})") (class "Default")
      (node (ref "R60") (pin "1") (pinfunction "1_1") (pintype "passive"))
      (node (ref "TP401") (pin "1") (pinfunction "1_1") (pintype "passive"))
      (node (ref "U8") (pin "12") (pinfunction "~{RESET}_12") (pintype "input"))
      (node (ref "U8") (pin "14") (pinfunction "~{SLEEP}_14") (pintype "input"))
    )
    (net (code "43") (name "Net-(U10-CP1)") (class "Default")
      (node (ref "C41") (pin "1") (pinfunction "1_1") (pintype "passive"))
      (node (ref "TP419") (pin "1") (pinfunction "1_1") (pintype "passive"))
      (node (ref "U10") (pin "4") (pinfunction "CP1_4") (pintype "passive"))
    )
    (net (code "44") (name "Net-(U10-CP2)") (class "Default")
      (node (ref "C41") (pin "2") (pinfunction "2_2") (pintype "passive"))
      (node (ref "TP420") (pin "1") (pinfunction "1_1") (pintype "passive"))
      (node (ref "U10") (pin "5") (pinfunction "CP2_5") (pintype "passive"))
    )
    (net (code "45") (name "Net-(U10-MS1)") (class "Default")
      (node (ref "R63") (pin "1") (pinfunction "1_1") (pintype "passive"))
      (node (ref "TP415") (pin "1") (pinfunction "1_1") (pintype "passive"))
      (node (ref "U10") (pin "10") (pinfunction "MS2_10") (pintype "input"))
      (node (ref "U10") (pin "11") (pinfunction "MS3_11") (pintype "input"))
      (node (ref "U10") (pin "9") (pinfunction "MS1_9") (pintype "input"))
    )
    (net (code "46") (name "Net-(U10-OUT1A)") (class "Default")
      (node (ref "L131") (pin "1") (pinfunction "1_1") (pintype "passive"))
      (node (ref "U10") (pin "24") (pinfunction "OUT1A_24") (pintype "output"))
    )
    (net (code "47") (name "Net-(U10-OUT1B)") (class "Default")
      (node (ref "L130") (pin "1") (pinfunction "1_1") (pintype "passive"))
      (node (ref "TP422") (pin "1") (pinfunction "1_1") (pintype "passive"))
      (node (ref "U10") (pin "21") (pinfunction "OUT1B_21") (pintype "output"))
    )
    (net (code "48") (name "Net-(U10-OUT2A)") (class "Default")
      (node (ref "L132") (pin "1") (pinfunction "1_1") (pintype "passive"))
      (node (ref "U10") (pin "26") (pinfunction "OUT2A_26") (pintype "output"))
    )
    (net (code "49") (name "Net-(U10-OUT2B)") (class "Default")
      (node (ref "L133") (pin "1") (pinfunction "1_1") (pintype "passive"))
      (node (ref "TP425") (pin "1") (pinfunction "1_1") (pintype "passive"))
      (node (ref "U10") (pin "1") (pinfunction "OUT2B_1") (pintype "output"))
    )
    (net (code "50") (name "Net-(U10-ROSC)") (class "Default")
      (node (ref "R82") (pin "1") (pinfunction "1_1") (pintype "passive"))
      (node (ref "R85") (pin "2") (pinfunction "2_2") (pintype "passive"))
      (node (ref "TP418") (pin "1") (pinfunction "1_1") (pintype "passive"))
      (node (ref "U10") (pin "13") (pinfunction "ROSC_13") (pintype "passive"))
    )
    (net (code "51") (name "Net-(U10-SENSE1)") (class "Default")
      (node (ref "R77") (pin "2") (pinfunction "2_2") (pintype "passive"))
      (node (ref "TP426") (pin "1") (pinfunction "1_1") (pintype "passive"))
      (node (ref "U10") (pin "23") (pinfunction "SENSE1_23") (pintype "passive"))
    )
    (net (code "52") (name "Net-(U10-SENSE2)") (class "Default")
      (node (ref "R76") (pin "2") (pinfunction "2_2") (pintype "passive"))
      (node (ref "TP427") (pin "1") (pinfunction "1_1") (pintype "passive"))
      (node (ref "U10") (pin "27") (pinfunction "SENSE2_27") (pintype "passive"))
    )
    (net (code "53") (name "Net-(U10-VCP)") (class "Default")
      (node (ref "C44") (pin "1") (pinfunction "1_1") (pintype "passive"))
      (node (ref "TP421") (pin "1") (pinfunction "1_1") (pintype "passive"))
      (node (ref "U10") (pin "6") (pinfunction "VCP_6") (pintype "passive"))
    )
    (net (code "54") (name "Net-(U10-VREG)") (class "Default")
      (node (ref "C49") (pin "2") (pinfunction "2_2") (pintype "passive"))
      (node (ref "TP417") (pin "1") (pinfunction "1_1") (pintype "passive"))
      (node (ref "U10") (pin "8") (pinfunction "VREG_8") (pintype "power_in"))
    )
    (net (code "55") (name "Net-(U10-~{RESET})") (class "Default")
      (node (ref "R62") (pin "1") (pinfunction "1_1") (pintype "passive"))
      (node (ref "TP416") (pin "1") (pinfunction "1_1") (pintype "passive"))
      (node (ref "U10") (pin "12") (pinfunction "~{RESET}_12") (pintype "input"))
      (node (ref "U10") (pin "14") (pinfunction "~{SLEEP}_14") (pintype "input"))
    )
    (net (code "56") (name "Net-(U11-CP1)") (class "Default")
      (node (ref "C42") (pin "1") (pinfunction "1_1") (pintype "passive"))
      (node (ref "TP441") (pin "1") (pinfunction "1_1") (pintype "passive"))
      (node (ref "U11") (pin "4") (pinfunction "CP1_4") (pintype "passive"))
    )
    (net (code "57") (name "Net-(U11-CP2)") (class "Default")
      (node (ref "C42") (pin "2") (pinfunction "2_2") (pintype "passive"))
      (node (ref "TP443") (pin "1") (pinfunction "1_1") (pintype "passive"))
      (node (ref "U11") (pin "5") (pinfunction "CP2_5") (pintype "passive"))
    )
    (net (code "58") (name "Net-(U11-MS1)") (class "Default")
      (node (ref "R65") (pin "1") (pinfunction "1_1") (pintype "passive"))
      (node (ref "TP428") (pin "1") (pinfunction "1_1") (pintype "passive"))
      (node (ref "TP442") (pin "1") (pinfunction "1_1") (pintype "passive"))
      (node (ref "U11") (pin "10") (pinfunction "MS2_10") (pintype "input"))
      (node (ref "U11") (pin "11") (pinfunction "MS3_11") (pintype "input"))
      (node (ref "U11") (pin "9") (pinfunction "MS1_9") (pintype "input"))
    )
    (net (code "59") (name "Net-(U11-OUT1A)") (class "Default")
      (node (ref "L141") (pin "1") (pinfunction "1_1") (pintype "passive"))
      (node (ref "U11") (pin "24") (pinfunction "OUT1A_24") (pintype "output"))
    )
    (net (code "60") (name "Net-(U11-OUT1B)") (class "Default")
      (node (ref "L140") (pin "1") (pinfunction "1_1") (pintype "passive"))
      (node (ref "TP435") (pin "1") (pinfunction "1_1") (pintype "passive"))
      (node (ref "U11") (pin "21") (pinfunction "OUT1B_21") (pintype "output"))
    )
    (net (code "61") (name "Net-(U11-OUT2A)") (class "Default")
      (node (ref "L142") (pin "1") (pinfunction "1_1") (pintype "passive"))
      (node (ref "U11") (pin "26") (pinfunction "OUT2A_26") (pintype "output"))
    )
    (net (code "62") (name "Net-(U11-OUT2B)") (class "Default")
      (node (ref "L143") (pin "1") (pinfunction "1_1") (pintype "passive"))
      (node (ref "TP438") (pin "1") (pinfunction "1_1") (pintype "passive"))
      (node (ref "U11") (pin "1") (pinfunction "OUT2B_1") (pintype "output"))
    )
    (net (code "63") (name "Net-(U11-ROSC)") (class "Default")
      (node (ref "R83") (pin "1") (pinfunction "1_1") (pintype "passive"))
      (node (ref "R86") (pin "2") (pinfunction "2_2") (pintype "passive"))
      (node (ref "TP433") (pin "1") (pinfunction "1_1") (pintype "passive"))
      (node (ref "U11") (pin "13") (pinfunction "ROSC_13") (pintype "passive"))
    )
    (net (code "64") (name "Net-(U11-SENSE1)") (class "Default")
      (node (ref "R80") (pin "2") (pinfunction "2_2") (pintype "passive"))
      (node (ref "TP439") (pin "1") (pinfunction "1_1") (pintype "passive"))
      (node (ref "U11") (pin "23") (pinfunction "SENSE1_23") (pintype "passive"))
    )
    (net (code "65") (name "Net-(U11-SENSE2)") (class "Default")
      (node (ref "R79") (pin "2") (pinfunction "2_2") (pintype "passive"))
      (node (ref "TP440") (pin "1") (pinfunction "1_1") (pintype "passive"))
      (node (ref "U11") (pin "27") (pinfunction "SENSE2_27") (pintype "passive"))
    )
    (net (code "66") (name "Net-(U11-VCP)") (class "Default")
      (node (ref "C45") (pin "1") (pinfunction "1_1") (pintype "passive"))
      (node (ref "TP434") (pin "1") (pinfunction "1_1") (pintype "passive"))
      (node (ref "U11") (pin "6") (pinfunction "VCP_6") (pintype "passive"))
    )
    (net (code "67") (name "Net-(U11-VREF)") (class "Default")
      (node (ref "C51") (pin "2") (pinfunction "2_2") (pintype "passive"))
      (node (ref "R72") (pin "2") (pinfunction "2_2") (pintype "passive"))
      (node (ref "R78") (pin "2") (pinfunction "2_2") (pintype "passive"))
      (node (ref "TP431") (pin "1") (pinfunction "1_1") (pintype "passive"))
      (node (ref "U11") (pin "17") (pinfunction "VREF_17") (pintype "input"))
    )
    (net (code "68") (name "Net-(U11-VREG)") (class "Default")
      (node (ref "C52") (pin "2") (pinfunction "2_2") (pintype "passive"))
      (node (ref "TP432") (pin "1") (pinfunction "1_1") (pintype "passive"))
      (node (ref "U11") (pin "8") (pinfunction "VREG_8") (pintype "power_in"))
    )
    (net (code "69") (name "Net-(U11-~{RESET})") (class "Default")
      (node (ref "R64") (pin "1") (pinfunction "1_1") (pintype "passive"))
      (node (ref "TP429") (pin "1") (pinfunction "1_1") (pintype "passive"))
      (node (ref "U11") (pin "12") (pinfunction "~{RESET}_12") (pintype "input"))
      (node (ref "U11") (pin "14") (pinfunction "~{SLEEP}_14") (pintype "input"))
    )
    (net (code "70") (name "unconnected-(U8-nc-Pad7)") (class "Default")
      (node (ref "U8") (pin "7") (pinfunction "nc_7") (pintype "passive"))
    )
    (net (code "71") (name "unconnected-(U8-nc-Pad20)") (class "Default")
      (node (ref "U8") (pin "20") (pinfunction "nc_20") (pintype "passive"))
    )
    (net (code "72") (name "unconnected-(U8-nc-Pad25)") (class "Default")
      (node (ref "U8") (pin "25") (pinfunction "nc_25") (pintype "passive"))
    )
    (net (code "73") (name "unconnected-(U10-nc-Pad7)") (class "Default")
      (node (ref "U10") (pin "7") (pinfunction "nc_7") (pintype "passive"))
    )
    (net (code "74") (name "unconnected-(U10-nc-Pad20)") (class "Default")
      (node (ref "U10") (pin "20") (pinfunction "nc_20") (pintype "passive"))
    )
    (net (code "75") (name "unconnected-(U10-nc-Pad25)") (class "Default")
      (node (ref "U10") (pin "25") (pinfunction "nc_25") (pintype "passive"))
    )
    (net (code "76") (name "unconnected-(U11-nc-Pad7)") (class "Default")
      (node (ref "U11") (pin "7") (pinfunction "nc_7") (pintype "passive"))
    )
    (net (code "77") (name "unconnected-(U11-nc-Pad20)") (class "Default")
      (node (ref "U11") (pin "20") (pinfunction "nc_20") (pintype "passive"))
    )
    (net (code "78") (name "unconnected-(U11-nc-Pad25)") (class "Default")
      (node (ref "U11") (pin "25") (pinfunction "nc_25") (pintype "passive"))
    )
  )
)
